# schematic_v2.net
KiCad netlist of a schematic drawn in EAGLE
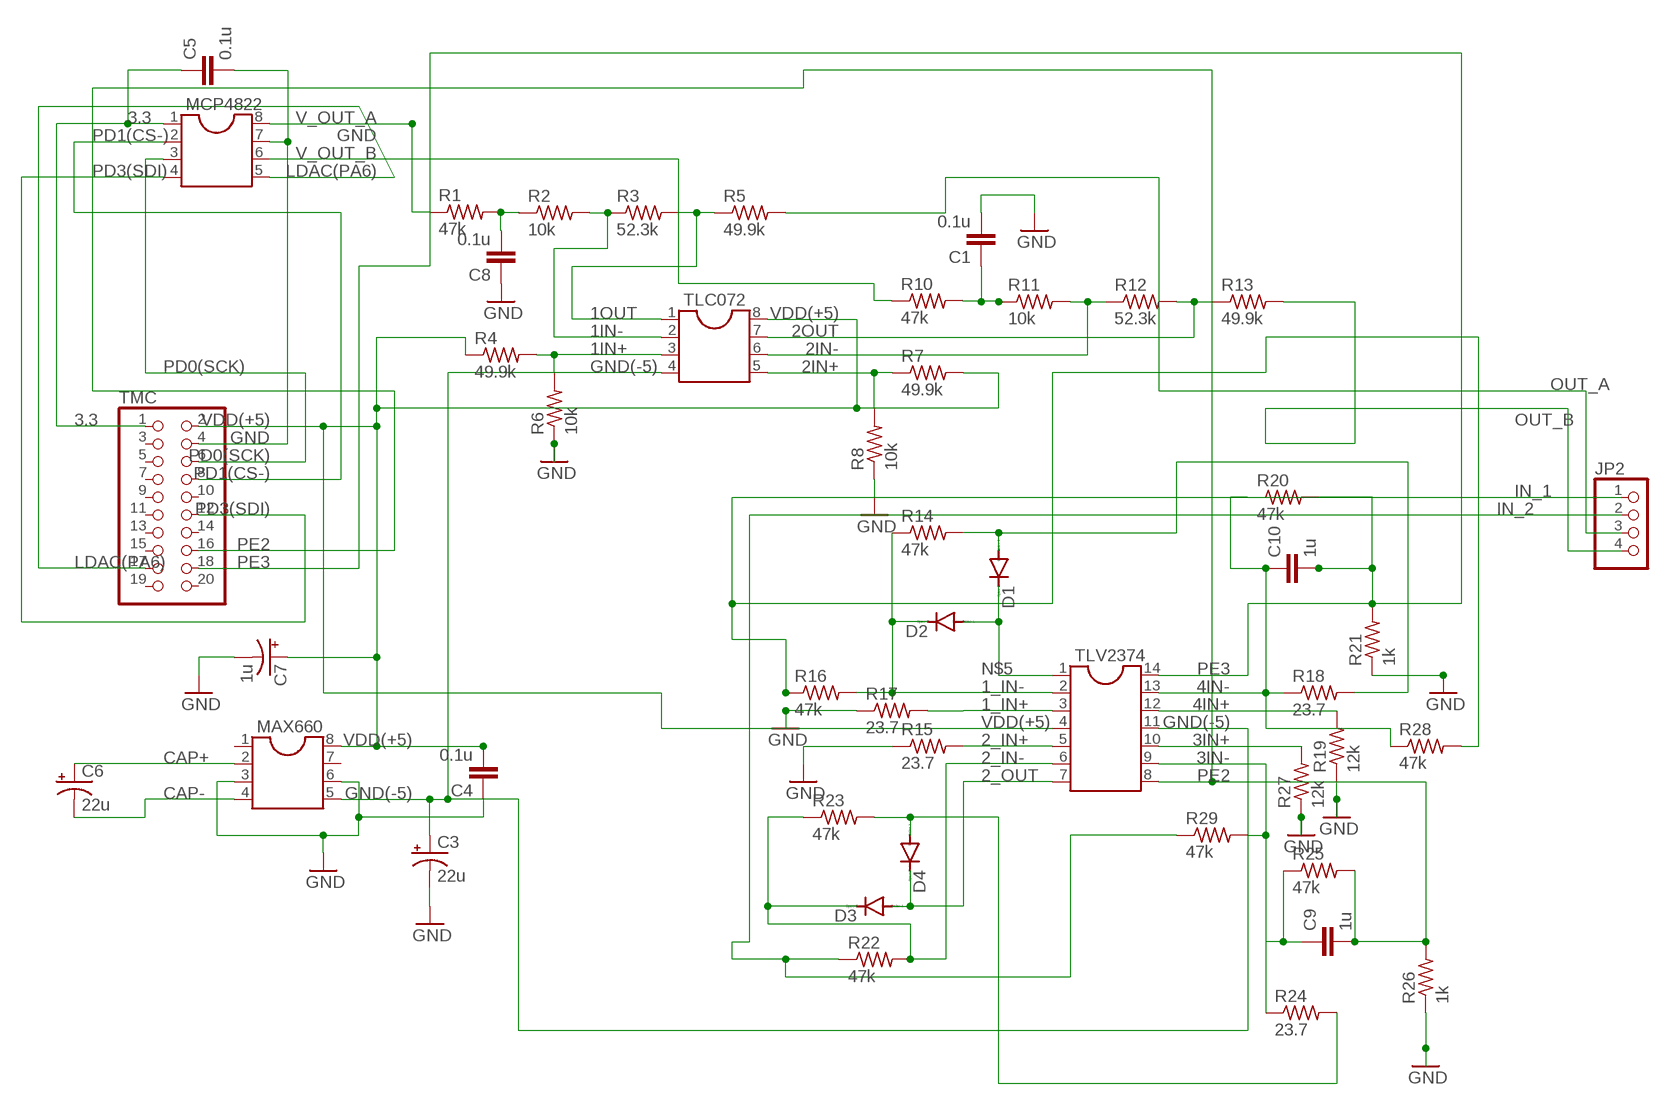
[diagram p0: schematic, sheet 1]

(export (version "E")
  (design (tool "Eeschema 10.0.6"))
  (components
    (comp (ref "C1")
      (value "0.1u")
      (footprint "eagle-import:C2.5-2")
      (libsource (lib "eagle-import") (part "C2.5/2"))
    )
    (comp (ref "C3")
      (value "22u")
      (footprint "eagle-import:E2,5-6")
      (libsource (lib "eagle-import") (part "CPOL-USE2.5-6"))
    )
    (comp (ref "C4")
      (value "0.1u")
      (footprint "eagle-import:C2.5-2")
      (libsource (lib "eagle-import") (part "C2.5/2"))
    )
    (comp (ref "C5")
      (value "0.1u")
      (footprint "eagle-import:C2.5-2")
      (libsource (lib "eagle-import") (part "C2.5/2"))
    )
    (comp (ref "C6")
      (value "22u")
      (footprint "eagle-import:E2,5-6")
      (libsource (lib "eagle-import") (part "CPOL-USE2.5-6"))
    )
    (comp (ref "C7")
      (value "1u")
      (footprint "eagle-import:E2,5-6")
      (libsource (lib "eagle-import") (part "CPOL-USE2.5-6"))
    )
    (comp (ref "C8")
      (value "0.1u")
      (footprint "eagle-import:C2.5-2")
      (libsource (lib "eagle-import") (part "C2.5/2"))
    )
    (comp (ref "C9")
      (value "1u")
      (footprint "eagle-import:C2.5-2")
      (libsource (lib "eagle-import") (part "C2.5/2"))
    )
    (comp (ref "C10")
      (value "1u")
      (footprint "eagle-import:C2.5-2")
      (libsource (lib "eagle-import") (part "C2.5/2"))
    )
    (comp (ref "D1")
      (value "1N4148DO35-7")
      (footprint "eagle-import:DO35-7")
      (libsource (lib "eagle-import") (part "1N4148DO35-7"))
    )
    (comp (ref "D2")
      (value "1N4148DO35-7")
      (footprint "eagle-import:DO35-7")
      (libsource (lib "eagle-import") (part "1N4148DO35-7"))
    )
    (comp (ref "D3")
      (value "1N4148DO35-7")
      (footprint "eagle-import:DO35-7")
      (libsource (lib "eagle-import") (part "1N4148DO35-7"))
    )
    (comp (ref "D4")
      (value "1N4148DO35-7")
      (footprint "eagle-import:DO35-7")
      (libsource (lib "eagle-import") (part "1N4148DO35-7"))
    )
    (comp (ref "JP2")
      (value "PINHD-1X4")
      (footprint "eagle-import:1X04")
      (libsource (lib "eagle-import") (part "PINHD-1X4"))
    )
    (comp (ref "MAX660")
      (value "DIL8")
      (footprint "eagle-import:DIL08")
      (libsource (lib "eagle-import") (part "DIL8"))
    )
    (comp (ref "MCP4822")
      (value "DIL8")
      (footprint "eagle-import:DIL08")
      (libsource (lib "eagle-import") (part "DIL8"))
    )
    (comp (ref "R1")
      (value "47k")
      (footprint "eagle-import:0207_10")
      (libsource (lib "eagle-import") (part "R-US_0207/10"))
    )
    (comp (ref "R2")
      (value "10k")
      (footprint "eagle-import:0207_10")
      (libsource (lib "eagle-import") (part "R-US_0207/10"))
    )
    (comp (ref "R3")
      (value "52.3k")
      (footprint "eagle-import:0207_10")
      (libsource (lib "eagle-import") (part "R-US_0207/10"))
    )
    (comp (ref "R4")
      (value "49.9k")
      (footprint "eagle-import:0207_10")
      (libsource (lib "eagle-import") (part "R-US_0207/10"))
    )
    (comp (ref "R5")
      (value "49.9k")
      (footprint "eagle-import:0207_10")
      (libsource (lib "eagle-import") (part "R-US_0207/10"))
    )
    (comp (ref "R6")
      (value "10k")
      (footprint "eagle-import:0207_10")
      (libsource (lib "eagle-import") (part "R-US_0207/10"))
    )
    (comp (ref "R7")
      (value "49.9k")
      (footprint "eagle-import:0207_10")
      (libsource (lib "eagle-import") (part "R-US_0207/10"))
    )
    (comp (ref "R8")
      (value "10k")
      (footprint "eagle-import:0207_10")
      (libsource (lib "eagle-import") (part "R-US_0207/10"))
    )
    (comp (ref "R10")
      (value "47k")
      (footprint "eagle-import:0207_10")
      (libsource (lib "eagle-import") (part "R-US_0207/10"))
    )
    (comp (ref "R11")
      (value "10k")
      (footprint "eagle-import:0207_10")
      (libsource (lib "eagle-import") (part "R-US_0207/10"))
    )
    (comp (ref "R12")
      (value "52.3k")
      (footprint "eagle-import:0207_10")
      (libsource (lib "eagle-import") (part "R-US_0207/10"))
    )
    (comp (ref "R13")
      (value "49.9k")
      (footprint "eagle-import:0207_10")
      (libsource (lib "eagle-import") (part "R-US_0207/10"))
    )
    (comp (ref "R14")
      (value "47k")
      (footprint "eagle-import:0207_10")
      (libsource (lib "eagle-import") (part "R-US_0207/10"))
    )
    (comp (ref "R15")
      (value "23.7")
      (footprint "eagle-import:0207_10")
      (libsource (lib "eagle-import") (part "R-US_0207/10"))
    )
    (comp (ref "R16")
      (value "47k")
      (footprint "eagle-import:0207_10")
      (libsource (lib "eagle-import") (part "R-US_0207/10"))
    )
    (comp (ref "R17")
      (value "23.7")
      (footprint "eagle-import:0207_10")
      (libsource (lib "eagle-import") (part "R-US_0207/10"))
    )
    (comp (ref "R18")
      (value "23.7")
      (footprint "eagle-import:0207_10")
      (libsource (lib "eagle-import") (part "R-US_0207/10"))
    )
    (comp (ref "R19")
      (value "12k")
      (footprint "eagle-import:0207_10")
      (libsource (lib "eagle-import") (part "R-US_0207/10"))
    )
    (comp (ref "R20")
      (value "47k")
      (footprint "eagle-import:0207_10")
      (libsource (lib "eagle-import") (part "R-US_0207/10"))
    )
    (comp (ref "R21")
      (value "1k")
      (footprint "eagle-import:0207_10")
      (libsource (lib "eagle-import") (part "R-US_0207/10"))
    )
    (comp (ref "R22")
      (value "47k")
      (footprint "eagle-import:0207_10")
      (libsource (lib "eagle-import") (part "R-US_0207/10"))
    )
    (comp (ref "R23")
      (value "47k")
      (footprint "eagle-import:0207_10")
      (libsource (lib "eagle-import") (part "R-US_0207/10"))
    )
    (comp (ref "R24")
      (value "23.7")
      (footprint "eagle-import:0207_10")
      (libsource (lib "eagle-import") (part "R-US_0207/10"))
    )
    (comp (ref "R25")
      (value "47k")
      (footprint "eagle-import:0207_10")
      (libsource (lib "eagle-import") (part "R-US_0207/10"))
    )
    (comp (ref "R26")
      (value "1k")
      (footprint "eagle-import:0207_10")
      (libsource (lib "eagle-import") (part "R-US_0207/10"))
    )
    (comp (ref "R27")
      (value "12k")
      (footprint "eagle-import:0207_10")
      (libsource (lib "eagle-import") (part "R-US_0207/10"))
    )
    (comp (ref "R28")
      (value "47k")
      (footprint "eagle-import:0207_10")
      (libsource (lib "eagle-import") (part "R-US_0207/10"))
    )
    (comp (ref "R29")
      (value "47k")
      (footprint "eagle-import:0207_10")
      (libsource (lib "eagle-import") (part "R-US_0207/10"))
    )
    (comp (ref "TLC072")
      (value "DIL8")
      (footprint "eagle-import:DIL08")
      (libsource (lib "eagle-import") (part "DIL8"))
    )
    (comp (ref "TLV2374")
      (value "DIL14")
      (footprint "eagle-import:DIL14")
      (libsource (lib "eagle-import") (part "DIL14"))
    )
    (comp (ref "TMC")
      (value "PINHD-2X10")
      (footprint "eagle-import:2X10")
      (libsource (lib "eagle-import") (part "PINHD-2X10"))
    )
  )
  (nets
    (net (code "1") (name "/1IN+") (class "Default")
      (node (ref "R4") (pin "2") (pinfunction "2_2") (pintype "passive"))
      (node (ref "R6") (pin "2") (pinfunction "2_2") (pintype "passive"))
      (node (ref "TLC072") (pin "3") (pinfunction "3_3") (pintype "passive"))
    )
    (net (code "2") (name "/1IN-") (class "Default")
      (node (ref "R2") (pin "2") (pinfunction "2_2") (pintype "passive"))
      (node (ref "R3") (pin "1") (pinfunction "1_1") (pintype "passive"))
      (node (ref "TLC072") (pin "2") (pinfunction "2_2") (pintype "passive"))
    )
    (net (code "3") (name "/1OUT") (class "Default")
      (node (ref "R3") (pin "2") (pinfunction "2_2") (pintype "passive"))
      (node (ref "R5") (pin "1") (pinfunction "1_1") (pintype "passive"))
      (node (ref "TLC072") (pin "1") (pinfunction "1_1") (pintype "passive"))
    )
    (net (code "4") (name "/1_IN+") (class "Default")
      (node (ref "R17") (pin "2") (pinfunction "2_2") (pintype "passive"))
      (node (ref "TLV2374") (pin "3") (pinfunction "3_3") (pintype "passive"))
    )
    (net (code "5") (name "/1_IN-") (class "Default")
      (node (ref "D2") (pin "C") (pinfunction "C_C") (pintype "passive"))
      (node (ref "R14") (pin "1") (pinfunction "1_1") (pintype "passive"))
      (node (ref "R16") (pin "2") (pinfunction "2_2") (pintype "passive"))
      (node (ref "TLV2374") (pin "2") (pinfunction "2_2") (pintype "passive"))
    )
    (net (code "6") (name "/2IN+") (class "Default")
      (node (ref "R7") (pin "1") (pinfunction "1_1") (pintype "passive"))
      (node (ref "R8") (pin "2") (pinfunction "2_2") (pintype "passive"))
      (node (ref "TLC072") (pin "5") (pinfunction "5_5") (pintype "passive"))
    )
    (net (code "7") (name "/2IN-") (class "Default")
      (node (ref "R11") (pin "2") (pinfunction "2_2") (pintype "passive"))
      (node (ref "R12") (pin "1") (pinfunction "1_1") (pintype "passive"))
      (node (ref "TLC072") (pin "6") (pinfunction "6_6") (pintype "passive"))
    )
    (net (code "8") (name "/2OUT") (class "Default")
      (node (ref "R12") (pin "2") (pinfunction "2_2") (pintype "passive"))
      (node (ref "R13") (pin "1") (pinfunction "1_1") (pintype "passive"))
      (node (ref "TLC072") (pin "7") (pinfunction "7_7") (pintype "passive"))
    )
    (net (code "9") (name "/2_IN+") (class "Default")
      (node (ref "R15") (pin "2") (pinfunction "2_2") (pintype "passive"))
      (node (ref "TLV2374") (pin "5") (pinfunction "5_5") (pintype "passive"))
    )
    (net (code "10") (name "/2_IN-") (class "Default")
      (node (ref "D3") (pin "C") (pinfunction "C_C") (pintype "passive"))
      (node (ref "R22") (pin "2") (pinfunction "2_2") (pintype "passive"))
      (node (ref "R23") (pin "1") (pinfunction "1_1") (pintype "passive"))
      (node (ref "TLV2374") (pin "6") (pinfunction "6_6") (pintype "passive"))
    )
    (net (code "11") (name "/2_OUT") (class "Default")
      (node (ref "D3") (pin "A") (pinfunction "A_A") (pintype "passive"))
      (node (ref "D4") (pin "C") (pinfunction "C_C") (pintype "passive"))
      (node (ref "TLV2374") (pin "7") (pinfunction "7_7") (pintype "passive"))
    )
    (net (code "12") (name "/3.3") (class "Default")
      (node (ref "C5") (pin "1") (pinfunction "1_1") (pintype "passive"))
      (node (ref "MCP4822") (pin "1") (pinfunction "1_1") (pintype "passive"))
      (node (ref "TMC") (pin "1") (pinfunction "1_1") (pintype "passive"))
    )
    (net (code "13") (name "/3IN+") (class "Default")
      (node (ref "R27") (pin "2") (pinfunction "2_2") (pintype "passive"))
      (node (ref "TLV2374") (pin "10") (pinfunction "10_10") (pintype "passive"))
    )
    (net (code "14") (name "/3IN-") (class "Default")
      (node (ref "C9") (pin "1") (pinfunction "1_1") (pintype "passive"))
      (node (ref "R24") (pin "1") (pinfunction "1_1") (pintype "passive"))
      (node (ref "R25") (pin "1") (pinfunction "1_1") (pintype "passive"))
      (node (ref "R29") (pin "2") (pinfunction "2_2") (pintype "passive"))
      (node (ref "TLV2374") (pin "9") (pinfunction "9_9") (pintype "passive"))
    )
    (net (code "15") (name "/4IN+") (class "Default")
      (node (ref "R19") (pin "2") (pinfunction "2_2") (pintype "passive"))
      (node (ref "TLV2374") (pin "12") (pinfunction "12_12") (pintype "passive"))
    )
    (net (code "16") (name "/4IN-") (class "Default")
      (node (ref "C10") (pin "1") (pinfunction "1_1") (pintype "passive"))
      (node (ref "R18") (pin "1") (pinfunction "1_1") (pintype "passive"))
      (node (ref "R20") (pin "1") (pinfunction "1_1") (pintype "passive"))
      (node (ref "R28") (pin "1") (pinfunction "1_1") (pintype "passive"))
      (node (ref "TLV2374") (pin "13") (pinfunction "13_13") (pintype "passive"))
    )
    (net (code "17") (name "/CAP+") (class "Default")
      (node (ref "C6") (pin "+") (pinfunction "+_+") (pintype "passive"))
      (node (ref "MAX660") (pin "2") (pinfunction "2_2") (pintype "passive"))
    )
    (net (code "18") (name "/CAP-") (class "Default")
      (node (ref "C6") (pin "-") (pinfunction "-_-") (pintype "passive"))
      (node (ref "MAX660") (pin "4") (pinfunction "4_4") (pintype "passive"))
    )
    (net (code "19") (name "/GND(-5)") (class "Default")
      (node (ref "C3") (pin "+") (pinfunction "+_+") (pintype "passive"))
      (node (ref "MAX660") (pin "5") (pinfunction "5_5") (pintype "passive"))
      (node (ref "TLC072") (pin "4") (pinfunction "4_4") (pintype "passive"))
      (node (ref "TLV2374") (pin "11") (pinfunction "11_11") (pintype "passive"))
    )
    (net (code "20") (name "/IN_1") (class "Default")
      (node (ref "JP2") (pin "1") (pinfunction "1_1") (pintype "passive"))
      (node (ref "R16") (pin "1") (pinfunction "1_1") (pintype "passive"))
      (node (ref "R28") (pin "2") (pinfunction "2_2") (pintype "passive"))
    )
    (net (code "21") (name "/IN_2") (class "Default")
      (node (ref "JP2") (pin "2") (pinfunction "2_2") (pintype "passive"))
      (node (ref "R22") (pin "1") (pinfunction "1_1") (pintype "passive"))
      (node (ref "R29") (pin "1") (pinfunction "1_1") (pintype "passive"))
    )
    (net (code "22") (name "/LDAC(PA6)") (class "Default")
      (node (ref "MCP4822") (pin "5") (pinfunction "5_5") (pintype "passive"))
      (node (ref "TMC") (pin "17") (pinfunction "17_17") (pintype "passive"))
    )
    (net (code "23") (name "/N$5") (class "Default")
      (node (ref "D1") (pin "C") (pinfunction "C_C") (pintype "passive"))
      (node (ref "D2") (pin "A") (pinfunction "A_A") (pintype "passive"))
      (node (ref "TLV2374") (pin "1") (pinfunction "1_1") (pintype "passive"))
    )
    (net (code "24") (name "/OUT_A") (class "Default")
      (node (ref "JP2") (pin "3") (pinfunction "3_3") (pintype "passive"))
      (node (ref "R5") (pin "2") (pinfunction "2_2") (pintype "passive"))
    )
    (net (code "25") (name "/OUT_B") (class "Default")
      (node (ref "JP2") (pin "4") (pinfunction "4_4") (pintype "passive"))
      (node (ref "R13") (pin "2") (pinfunction "2_2") (pintype "passive"))
    )
    (net (code "26") (name "/PD0(SCK)") (class "Default")
      (node (ref "MCP4822") (pin "3") (pinfunction "3_3") (pintype "passive"))
      (node (ref "TMC") (pin "6") (pinfunction "6_6") (pintype "passive"))
    )
    (net (code "27") (name "/PD1(CS-)") (class "Default")
      (node (ref "MCP4822") (pin "2") (pinfunction "2_2") (pintype "passive"))
      (node (ref "TMC") (pin "8") (pinfunction "8_8") (pintype "passive"))
    )
    (net (code "28") (name "/PD3(SDI)") (class "Default")
      (node (ref "MCP4822") (pin "4") (pinfunction "4_4") (pintype "passive"))
      (node (ref "TMC") (pin "12") (pinfunction "12_12") (pintype "passive"))
    )
    (net (code "29") (name "/PE2") (class "Default")
      (node (ref "C9") (pin "2") (pinfunction "2_2") (pintype "passive"))
      (node (ref "R25") (pin "2") (pinfunction "2_2") (pintype "passive"))
      (node (ref "R26") (pin "2") (pinfunction "2_2") (pintype "passive"))
      (node (ref "TLV2374") (pin "8") (pinfunction "8_8") (pintype "passive"))
      (node (ref "TMC") (pin "16") (pinfunction "16_16") (pintype "passive"))
    )
    (net (code "30") (name "/PE3") (class "Default")
      (node (ref "C10") (pin "2") (pinfunction "2_2") (pintype "passive"))
      (node (ref "R20") (pin "2") (pinfunction "2_2") (pintype "passive"))
      (node (ref "R21") (pin "2") (pinfunction "2_2") (pintype "passive"))
      (node (ref "TLV2374") (pin "14") (pinfunction "14_14") (pintype "passive"))
      (node (ref "TMC") (pin "18") (pinfunction "18_18") (pintype "passive"))
    )
    (net (code "31") (name "/VDD(+5)") (class "Default")
      (node (ref "C4") (pin "2") (pinfunction "2_2") (pintype "passive"))
      (node (ref "C7") (pin "+") (pinfunction "+_+") (pintype "passive"))
      (node (ref "MAX660") (pin "8") (pinfunction "8_8") (pintype "passive"))
      (node (ref "R4") (pin "1") (pinfunction "1_1") (pintype "passive"))
      (node (ref "R7") (pin "2") (pinfunction "2_2") (pintype "passive"))
      (node (ref "TLC072") (pin "8") (pinfunction "8_8") (pintype "passive"))
      (node (ref "TLV2374") (pin "4") (pinfunction "4_4") (pintype "passive"))
      (node (ref "TMC") (pin "2") (pinfunction "2_2") (pintype "passive"))
    )
    (net (code "32") (name "/V_OUT_A") (class "Default")
      (node (ref "MCP4822") (pin "8") (pinfunction "8_8") (pintype "passive"))
      (node (ref "R1") (pin "1") (pinfunction "1_1") (pintype "passive"))
    )
    (net (code "33") (name "/V_OUT_B") (class "Default")
      (node (ref "MCP4822") (pin "6") (pinfunction "6_6") (pintype "passive"))
      (node (ref "R10") (pin "1") (pinfunction "1_1") (pintype "passive"))
    )
    (net (code "34") (name "GND") (class "Default")
      (node (ref "C1") (pin "2") (pinfunction "2_2") (pintype "passive"))
      (node (ref "C3") (pin "-") (pinfunction "-_-") (pintype "passive"))
      (node (ref "C4") (pin "1") (pinfunction "1_1") (pintype "passive"))
      (node (ref "C5") (pin "2") (pinfunction "2_2") (pintype "passive"))
      (node (ref "C7") (pin "-") (pinfunction "-_-") (pintype "passive"))
      (node (ref "C8") (pin "1") (pinfunction "1_1") (pintype "passive"))
      (node (ref "MAX660") (pin "3") (pinfunction "3_3") (pintype "passive"))
      (node (ref "MAX660") (pin "6") (pinfunction "6_6") (pintype "passive"))
      (node (ref "MCP4822") (pin "7") (pinfunction "7_7") (pintype "passive"))
      (node (ref "R15") (pin "1") (pinfunction "1_1") (pintype "passive"))
      (node (ref "R17") (pin "1") (pinfunction "1_1") (pintype "passive"))
      (node (ref "R19") (pin "1") (pinfunction "1_1") (pintype "passive"))
      (node (ref "R21") (pin "1") (pinfunction "1_1") (pintype "passive"))
      (node (ref "R26") (pin "1") (pinfunction "1_1") (pintype "passive"))
      (node (ref "R27") (pin "1") (pinfunction "1_1") (pintype "passive"))
      (node (ref "R6") (pin "1") (pinfunction "1_1") (pintype "passive"))
      (node (ref "R8") (pin "1") (pinfunction "1_1") (pintype "passive"))
      (node (ref "TMC") (pin "4") (pinfunction "4_4") (pintype "passive"))
    )
    (net (code "35") (name "Net-(C8-Pad2)") (class "Default")
      (node (ref "C8") (pin "2") (pinfunction "2_2") (pintype "passive"))
      (node (ref "R1") (pin "2") (pinfunction "2_2") (pintype "passive"))
      (node (ref "R2") (pin "1") (pinfunction "1_1") (pintype "passive"))
    )
    (net (code "36") (name "Net-(D1-PadA)") (class "Default")
      (node (ref "D1") (pin "A") (pinfunction "A_A") (pintype "passive"))
      (node (ref "R14") (pin "2") (pinfunction "2_2") (pintype "passive"))
      (node (ref "R18") (pin "2") (pinfunction "2_2") (pintype "passive"))
    )
    (net (code "37") (name "Net-(D4-PadA)") (class "Default")
      (node (ref "D4") (pin "A") (pinfunction "A_A") (pintype "passive"))
      (node (ref "R23") (pin "2") (pinfunction "2_2") (pintype "passive"))
      (node (ref "R24") (pin "2") (pinfunction "2_2") (pintype "passive"))
    )
    (net (code "38") (name "Net-(R10-Pad2)") (class "Default")
      (node (ref "R10") (pin "2") (pinfunction "2_2") (pintype "passive"))
      (node (ref "R11") (pin "1") (pinfunction "1_1") (pintype "passive"))
    )
    (net (code "39") (name "unconnected-(C1-Pad1)") (class "Default")
      (node (ref "C1") (pin "1") (pinfunction "1_1") (pintype "passive"))
    )
    (net (code "40") (name "unconnected-(MAX660-Pad1)") (class "Default")
      (node (ref "MAX660") (pin "1") (pinfunction "1_1") (pintype "passive"))
    )
    (net (code "41") (name "unconnected-(MAX660-Pad7)") (class "Default")
      (node (ref "MAX660") (pin "7") (pinfunction "7_7") (pintype "passive"))
    )
    (net (code "42") (name "unconnected-(TMC-Pad3)") (class "Default")
      (node (ref "TMC") (pin "3") (pinfunction "3_3") (pintype "passive"))
    )
    (net (code "43") (name "unconnected-(TMC-Pad5)") (class "Default")
      (node (ref "TMC") (pin "5") (pinfunction "5_5") (pintype "passive"))
    )
    (net (code "44") (name "unconnected-(TMC-Pad7)") (class "Default")
      (node (ref "TMC") (pin "7") (pinfunction "7_7") (pintype "passive"))
    )
    (net (code "45") (name "unconnected-(TMC-Pad9)") (class "Default")
      (node (ref "TMC") (pin "9") (pinfunction "9_9") (pintype "passive"))
    )
    (net (code "46") (name "unconnected-(TMC-Pad10)") (class "Default")
      (node (ref "TMC") (pin "10") (pinfunction "10_10") (pintype "passive"))
    )
    (net (code "47") (name "unconnected-(TMC-Pad11)") (class "Default")
      (node (ref "TMC") (pin "11") (pinfunction "11_11") (pintype "passive"))
    )
    (net (code "48") (name "unconnected-(TMC-Pad13)") (class "Default")
      (node (ref "TMC") (pin "13") (pinfunction "13_13") (pintype "passive"))
    )
    (net (code "49") (name "unconnected-(TMC-Pad14)") (class "Default")
      (node (ref "TMC") (pin "14") (pinfunction "14_14") (pintype "passive"))
    )
    (net (code "50") (name "unconnected-(TMC-Pad15)") (class "Default")
      (node (ref "TMC") (pin "15") (pinfunction "15_15") (pintype "passive"))
    )
    (net (code "51") (name "unconnected-(TMC-Pad19)") (class "Default")
      (node (ref "TMC") (pin "19") (pinfunction "19_19") (pintype "passive"))
    )
    (net (code "52") (name "unconnected-(TMC-Pad20)") (class "Default")
      (node (ref "TMC") (pin "20") (pinfunction "20_20") (pintype "passive"))
    )
  )
)
